# HRsensorFlex.net
KiCad netlist of a schematic drawn in EAGLE
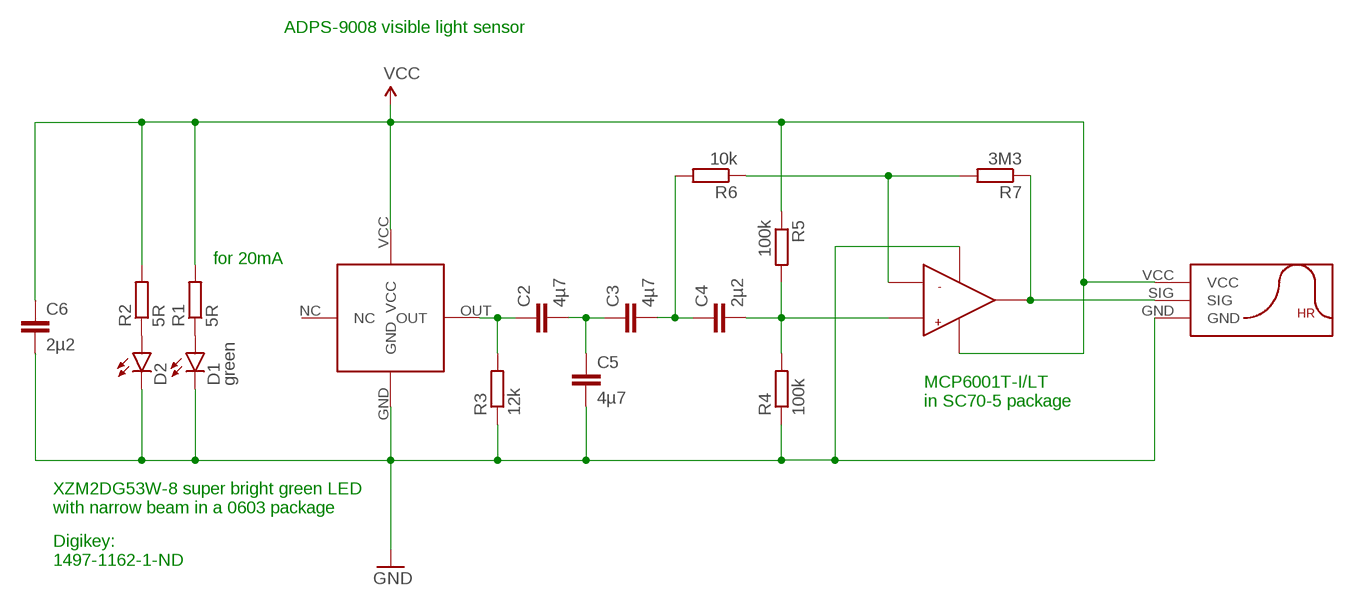
[diagram p0: schematic, sheet 1]

(export (version "E")
  (design (tool "Eeschema 10.0.6"))
  (components
    (comp (ref "C2")
      (value "4µ7")
      (footprint "eagle-import:C0402")
      (libsource (lib "eagle-import") (part "C-EUC0402"))
    )
    (comp (ref "C3")
      (value "4µ7")
      (footprint "eagle-import:C0402")
      (libsource (lib "eagle-import") (part "C-EUC0402"))
    )
    (comp (ref "C4")
      (value "2µ2")
      (footprint "eagle-import:C0402")
      (libsource (lib "eagle-import") (part "C-EUC0402"))
    )
    (comp (ref "C5")
      (value "4µ7")
      (footprint "eagle-import:C0402")
      (libsource (lib "eagle-import") (part "C-EUC0402"))
    )
    (comp (ref "C6")
      (value "2µ2")
      (footprint "eagle-import:C0402")
      (libsource (lib "eagle-import") (part "C-EUC0402"))
    )
    (comp (ref "D1")
      (value "green")
      (footprint "eagle-import:LED-0603")
      (libsource (lib "eagle-import") (part "LED0603"))
    )
    (comp (ref "D2")
      (value "LED0603")
      (footprint "eagle-import:LED-0603")
      (libsource (lib "eagle-import") (part "LED0603"))
    )
    (comp (ref "R1")
      (value "5R")
      (footprint "eagle-import:R0402")
      (libsource (lib "eagle-import") (part "R-EU_R0402"))
    )
    (comp (ref "R2")
      (value "5R")
      (footprint "eagle-import:R0402")
      (libsource (lib "eagle-import") (part "R-EU_R0402"))
    )
    (comp (ref "R3")
      (value "12k")
      (footprint "eagle-import:R0402")
      (libsource (lib "eagle-import") (part "R-EU_R0402"))
    )
    (comp (ref "R4")
      (value "100k")
      (footprint "eagle-import:R0402")
      (libsource (lib "eagle-import") (part "R-EU_R0402"))
    )
    (comp (ref "R5")
      (value "100k")
      (footprint "eagle-import:R0402")
      (libsource (lib "eagle-import") (part "R-EU_R0402"))
    )
    (comp (ref "R6")
      (value "10k")
      (footprint "eagle-import:R0402")
      (libsource (lib "eagle-import") (part "R-EU_R0402"))
    )
    (comp (ref "R7")
      (value "3M3")
      (footprint "eagle-import:R0402")
      (libsource (lib "eagle-import") (part "R-EU_R0402"))
    )
    (comp (ref "U$1")
      (value "MCP6001")
      (footprint "eagle-import:SC70-5L")
      (libsource (lib "eagle-import") (part "MCP6001"))
    )
    (comp (ref "U$2")
      (value "APDS-9008")
      (footprint "eagle-import:APDS9008")
      (libsource (lib "eagle-import") (part "APDS-9008"))
    )
    (comp (ref "U$3")
      (value "HR_PADS")
      (footprint "eagle-import:HR_PADS")
      (libsource (lib "eagle-import") (part "HR_PADS"))
    )
  )
  (nets
    (net (code "1") (name "GND") (class "Default")
      (node (ref "C5") (pin "2") (pinfunction "2_2") (pintype "passive"))
      (node (ref "C6") (pin "2") (pinfunction "2_2") (pintype "passive"))
      (node (ref "D1") (pin "C") (pinfunction "C_C") (pintype "passive"))
      (node (ref "D2") (pin "C") (pinfunction "C_C") (pintype "passive"))
      (node (ref "R3") (pin "1") (pinfunction "1_1") (pintype "passive"))
      (node (ref "R4") (pin "1") (pinfunction "1_1") (pintype "passive"))
      (node (ref "U$1") (pin "2") (pinfunction "VSS_2") (pintype "bidirectional"))
      (node (ref "U$2") (pin "GND") (pinfunction "GND_GND") (pintype "bidirectional"))
      (node (ref "U$3") (pin "GND") (pinfunction "GND_GND") (pintype "bidirectional"))
    )
    (net (code "2") (name "Net-(C2-Pad1)") (class "Default")
      (node (ref "C2") (pin "1") (pinfunction "1_1") (pintype "passive"))
      (node (ref "R3") (pin "2") (pinfunction "2_2") (pintype "passive"))
      (node (ref "U$2") (pin "OUT") (pinfunction "OUT_OUT") (pintype "bidirectional"))
    )
    (net (code "3") (name "Net-(C2-Pad2)") (class "Default")
      (node (ref "C2") (pin "2") (pinfunction "2_2") (pintype "passive"))
      (node (ref "C3") (pin "1") (pinfunction "1_1") (pintype "passive"))
      (node (ref "C5") (pin "1") (pinfunction "1_1") (pintype "passive"))
    )
    (net (code "4") (name "Net-(C3-Pad2)") (class "Default")
      (node (ref "C3") (pin "2") (pinfunction "2_2") (pintype "passive"))
      (node (ref "C4") (pin "1") (pinfunction "1_1") (pintype "passive"))
      (node (ref "R6") (pin "2") (pinfunction "2_2") (pintype "passive"))
    )
    (net (code "5") (name "Net-(D1-PadA)") (class "Default")
      (node (ref "D1") (pin "A") (pinfunction "A_A") (pintype "passive"))
      (node (ref "R1") (pin "1") (pinfunction "1_1") (pintype "passive"))
    )
    (net (code "6") (name "Net-(D2-PadA)") (class "Default")
      (node (ref "D2") (pin "A") (pinfunction "A_A") (pintype "passive"))
      (node (ref "R2") (pin "1") (pinfunction "1_1") (pintype "passive"))
    )
    (net (code "7") (name "Net-(U$1-+)") (class "Default")
      (node (ref "C4") (pin "2") (pinfunction "2_2") (pintype "passive"))
      (node (ref "R4") (pin "2") (pinfunction "2_2") (pintype "passive"))
      (node (ref "R5") (pin "2") (pinfunction "2_2") (pintype "passive"))
      (node (ref "U$1") (pin "3") (pinfunction "+_3") (pintype "bidirectional"))
    )
    (net (code "8") (name "Net-(U$1--)") (class "Default")
      (node (ref "R6") (pin "1") (pinfunction "1_1") (pintype "passive"))
      (node (ref "R7") (pin "2") (pinfunction "2_2") (pintype "passive"))
      (node (ref "U$1") (pin "4") (pinfunction "-_4") (pintype "bidirectional"))
    )
    (net (code "9") (name "Net-(U$1-OUT)") (class "Default")
      (node (ref "R7") (pin "1") (pinfunction "1_1") (pintype "passive"))
      (node (ref "U$1") (pin "1") (pinfunction "OUT_1") (pintype "bidirectional"))
      (node (ref "U$3") (pin "SIG") (pinfunction "SIG_SIG") (pintype "bidirectional"))
    )
    (net (code "10") (name "VCC") (class "Default")
      (node (ref "C6") (pin "1") (pinfunction "1_1") (pintype "passive"))
      (node (ref "R1") (pin "2") (pinfunction "2_2") (pintype "passive"))
      (node (ref "R2") (pin "2") (pinfunction "2_2") (pintype "passive"))
      (node (ref "R5") (pin "1") (pinfunction "1_1") (pintype "passive"))
      (node (ref "U$1") (pin "5") (pinfunction "VDD_5") (pintype "bidirectional"))
      (node (ref "U$2") (pin "VCC") (pinfunction "VCC_VCC") (pintype "bidirectional"))
      (node (ref "U$3") (pin "VCC") (pinfunction "VCC_VCC") (pintype "bidirectional"))
    )
    (net (code "11") (name "unconnected-(U$2-PadNC)") (class "Default")
      (node (ref "U$2") (pin "NC") (pinfunction "NC_NC") (pintype "bidirectional"))
    )
  )
)
